# MCU_PSoC_Rev1_1.net
KiCad netlist of a schematic drawn in Altium Designer
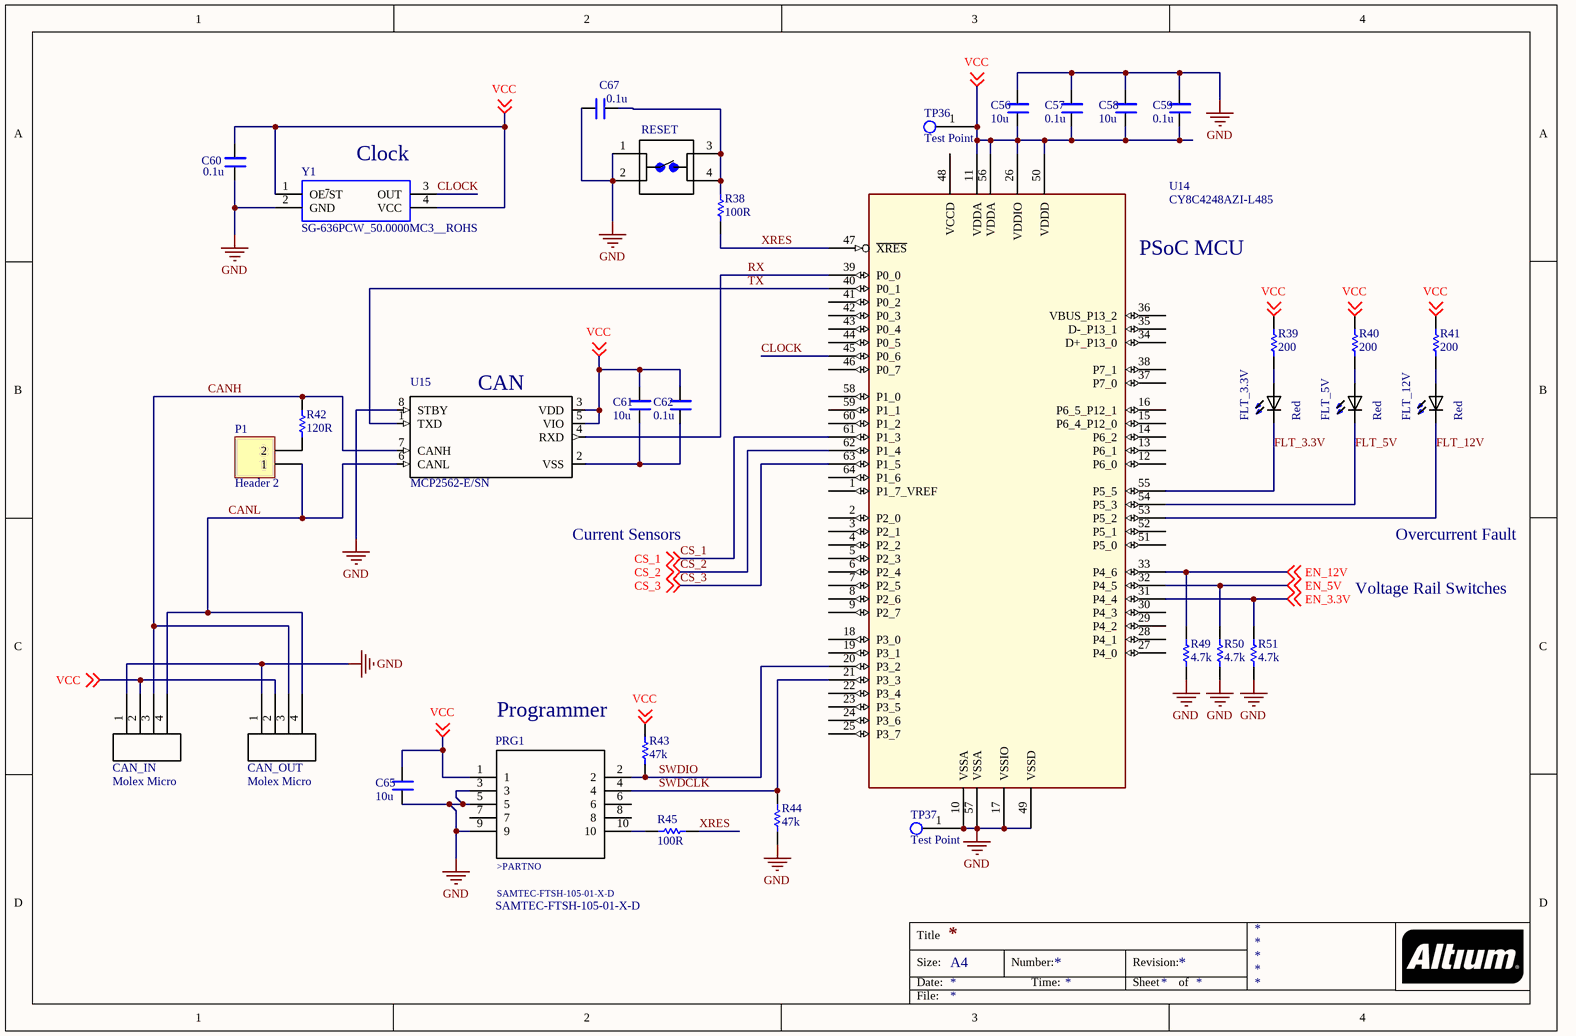
[diagram p0: MCU_PSoC_Rev1.1.SchDoc]

(export (version "E")
  (design (tool "Eeschema 10.0.6"))
  (components
    (comp (ref "C56")
      (value "10u")
      (footprint "*CAPC2012X88N")
      (description "100pF Â±5% 250V Ceramic Capacitor C0G, NP0 0805 _2012 Metric_")
      (fields (field (name "MF") "KEMET") (field (name "DIGI-KEY_PART_NUMBER") "399-15000-1-ND"))
      (libsource (lib "C0805C101JAGAC7800") (part "C0805C101JAGAC7800"))
    )
    (comp (ref "C57")
      (value "0.1u")
      (footprint "*CAPC2012X88N")
      (description "100pF Â±5% 250V Ceramic Capacitor C0G, NP0 0805 _2012 Metric_")
      (fields (field (name "MF") "KEMET") (field (name "DIGI-KEY_PART_NUMBER") "399-15000-1-ND"))
      (libsource (lib "C0805C101JAGAC7800") (part "C0805C101JAGAC7800"))
    )
    (comp (ref "C58")
      (value "10u")
      (footprint "*CAPC2012X88N")
      (description "100pF Â±5% 250V Ceramic Capacitor C0G, NP0 0805 _2012 Metric_")
      (fields (field (name "MF") "KEMET") (field (name "DIGI-KEY_PART_NUMBER") "399-15000-1-ND"))
      (libsource (lib "C0805C101JAGAC7800") (part "C0805C101JAGAC7800"))
    )
    (comp (ref "C59")
      (value "0.1u")
      (footprint "*CAPC2012X88N")
      (description "100pF Â±5% 250V Ceramic Capacitor C0G, NP0 0805 _2012 Metric_")
      (fields (field (name "MF") "KEMET") (field (name "DIGI-KEY_PART_NUMBER") "399-15000-1-ND"))
      (libsource (lib "C0805C101JAGAC7800") (part "C0805C101JAGAC7800"))
    )
    (comp (ref "C60")
      (value "0.1u")
      (footprint "*CAPC2012X88N")
      (description "100pF Â±5% 250V Ceramic Capacitor C0G, NP0 0805 _2012 Metric_")
      (fields (field (name "MF") "KEMET") (field (name "DIGI-KEY_PART_NUMBER") "399-15000-1-ND"))
      (libsource (lib "C0805C101JAGAC7800") (part "C0805C101JAGAC7800"))
    )
    (comp (ref "C61")
      (value "10u")
      (footprint "*CAPC2012X88N")
      (description "100pF Â±5% 250V Ceramic Capacitor C0G, NP0 0805 _2012 Metric_")
      (fields (field (name "MF") "KEMET") (field (name "DIGI-KEY_PART_NUMBER") "399-15000-1-ND"))
      (libsource (lib "C0805C101JAGAC7800") (part "C0805C101JAGAC7800"))
    )
    (comp (ref "C62")
      (value "0.1u")
      (footprint "*CAPC2012X88N")
      (description "100pF Â±5% 250V Ceramic Capacitor C0G, NP0 0805 _2012 Metric_")
      (fields (field (name "MF") "KEMET") (field (name "DIGI-KEY_PART_NUMBER") "399-15000-1-ND"))
      (libsource (lib "C0805C101JAGAC7800") (part "C0805C101JAGAC7800"))
    )
    (comp (ref "C65")
      (value "10u")
      (footprint "*CAPC2012X88N")
      (description "100pF Â±5% 250V Ceramic Capacitor C0G, NP0 0805 _2012 Metric_")
      (fields (field (name "MF") "KEMET") (field (name "DIGI-KEY_PART_NUMBER") "399-15000-1-ND"))
      (libsource (lib "C0805C101JAGAC7800") (part "C0805C101JAGAC7800"))
    )
    (comp (ref "C67")
      (value "0.1u")
      (footprint "*CAPC2012X88N")
      (description "100pF Â±5% 250V Ceramic Capacitor C0G, NP0 0805 _2012 Metric_")
      (fields (field (name "MF") "KEMET") (field (name "DIGI-KEY_PART_NUMBER") "399-15000-1-ND"))
      (libsource (lib "C0805C101JAGAC7800") (part "C0805C101JAGAC7800"))
    )
    (comp (ref "CAN_IN")
      (value "Molex Micro")
      (footprint "0430450427")
      (description "Molex micro-fit 3.0 dual row header. P/N 0430450427")
      (libsource (lib "Connector Schematic Symbols") (part "Molex micro-fit 4-pin (Single row schematic)"))
    )
    (comp (ref "CAN_OUT")
      (value "Molex Micro")
      (footprint "0430450427")
      (description "Molex micro-fit 3.0 dual row header. P/N 0430450427")
      (libsource (lib "Connector Schematic Symbols") (part "Molex micro-fit 4-pin (Single row schematic)"))
    )
    (comp (ref "FLT_3.3V")
      (value "Red")
      (footprint "*DIOC200X125X110_LTST-C171KSKT(Primary)")
      (description "Yellow 2 x 1.25 x 0.8 mm 130Â° Water Clear 50 mcd 2 V LED SMT")
      (fields (field (name "MP") "LTST-C171KSKT") (field (name "DIGI-KEY_PART_NUMBER") "160-1428-1-ND"))
      (libsource (lib "LTST-C171KSKT") (part "LTST-C171KSKT"))
    )
    (comp (ref "FLT_5V")
      (value "Red")
      (footprint "*DIOC200X125X110_LTST-C171KSKT(Primary)")
      (description "Yellow 2 x 1.25 x 0.8 mm 130Â° Water Clear 50 mcd 2 V LED SMT")
      (fields (field (name "MP") "LTST-C171KSKT") (field (name "DIGI-KEY_PART_NUMBER") "160-1428-1-ND"))
      (libsource (lib "LTST-C171KSKT") (part "LTST-C171KSKT"))
    )
    (comp (ref "FLT_12V")
      (value "Red")
      (footprint "*DIOC200X125X110_LTST-C171KSKT(Primary)")
      (description "Yellow 2 x 1.25 x 0.8 mm 130Â° Water Clear 50 mcd 2 V LED SMT")
      (fields (field (name "MP") "LTST-C171KSKT") (field (name "DIGI-KEY_PART_NUMBER") "160-1428-1-ND"))
      (libsource (lib "LTST-C171KSKT") (part "LTST-C171KSKT"))
    )
    (comp (ref "P1")
      (value "Header 2")
      (footprint "HDR1X2")
      (description "Header, 2-Pin")
      (fields (field (name "PUBLISHER") "Altium Limited"))
      (libsource (lib "Power Distribution") (part "Header 2"))
    )
    (comp (ref "PRG1")
      (value "SAMTEC-FTSH-105-01-X-D")
      (footprint "SAMTEC-FTSH-105-01-X-D")
      (description "SAMTEC-FTSH-105-01-X-D. Shrouded 10-pin header with .05 in pitch.")
      (libsource (lib "Power Distribution") (part "SAMTEC-FTSH-105-01-X-D"))
    )
    (comp (ref "R38")
      (value "100R")
      (footprint "RESC0805(2012)_M")
      (description "8M06 0.125W 1% 0805 (2012 Metric)  SMD")
      (fields (field (name "POWER") "0.125 W") (field (name "TOLERANCE") "1 %"))
      (libsource (lib "Altium Content Vault") (part "RES"))
    )
    (comp (ref "R39")
      (value "200")
      (footprint "RESC0805(2012)_M")
      (description "8M06 0.125W 1% 0805 (2012 Metric)  SMD")
      (fields (field (name "POWER") "0.125 W") (field (name "TOLERANCE") "1 %"))
      (libsource (lib "Altium Content Vault") (part "RES"))
    )
    (comp (ref "R40")
      (value "200")
      (footprint "RESC0805(2012)_M")
      (description "8M06 0.125W 1% 0805 (2012 Metric)  SMD")
      (fields (field (name "POWER") "0.125 W") (field (name "TOLERANCE") "1 %"))
      (libsource (lib "Altium Content Vault") (part "RES"))
    )
    (comp (ref "R41")
      (value "200")
      (footprint "RESC0805(2012)_M")
      (description "8M06 0.125W 1% 0805 (2012 Metric)  SMD")
      (fields (field (name "POWER") "0.125 W") (field (name "TOLERANCE") "1 %"))
      (libsource (lib "Altium Content Vault") (part "RES"))
    )
    (comp (ref "R42")
      (value "120R")
      (footprint "RESC0805(2012)_N")
      (description "120R 0.125W 5% 0805 (2012 Metric)  SMD")
      (fields (field (name "TOLERANCE") "5 %") (field (name "POWER") "0.125 W"))
      (libsource (lib "CAN Termination Resistor 0805") (part "120R 5% 0805"))
    )
    (comp (ref "R43")
      (value "47k")
      (footprint "RESC0805(2012)_M")
      (description "8M06 0.125W 1% 0805 (2012 Metric)  SMD")
      (fields (field (name "POWER") "0.125 W") (field (name "TOLERANCE") "1 %"))
      (libsource (lib "Altium Content Vault") (part "RES"))
    )
    (comp (ref "R44")
      (value "47k")
      (footprint "RESC0805(2012)_M")
      (description "8M06 0.125W 1% 0805 (2012 Metric)  SMD")
      (fields (field (name "POWER") "0.125 W") (field (name "TOLERANCE") "1 %"))
      (libsource (lib "Altium Content Vault") (part "RES"))
    )
    (comp (ref "R45")
      (value "100R")
      (footprint "RESC0805(2012)_M")
      (description "8M06 0.125W 1% 0805 (2012 Metric)  SMD")
      (fields (field (name "POWER") "0.125 W") (field (name "TOLERANCE") "1 %"))
      (libsource (lib "Altium Content Vault") (part "RES"))
    )
    (comp (ref "R49")
      (value "4.7k")
      (footprint "RESC0805(2012)_M")
      (description "8M06 0.125W 1% 0805 (2012 Metric)  SMD")
      (fields (field (name "POWER") "0.125 W") (field (name "TOLERANCE") "1 %"))
      (libsource (lib "Altium Content Vault") (part "RES"))
    )
    (comp (ref "R50")
      (value "4.7k")
      (footprint "RESC0805(2012)_M")
      (description "8M06 0.125W 1% 0805 (2012 Metric)  SMD")
      (fields (field (name "POWER") "0.125 W") (field (name "TOLERANCE") "1 %"))
      (libsource (lib "Altium Content Vault") (part "RES"))
    )
    (comp (ref "R51")
      (value "4.7k")
      (footprint "RESC0805(2012)_M")
      (description "8M06 0.125W 1% 0805 (2012 Metric)  SMD")
      (fields (field (name "POWER") "0.125 W") (field (name "TOLERANCE") "1 %"))
      (libsource (lib "Altium Content Vault") (part "RES"))
    )
    (comp (ref "RESET")
      (value "1825910-7")
      (footprint "Switch 6mm 24V (NO)")
      (description "FSM4JAH=6MM TACT SWITCH, HIGH TEMP")
      (fields (field (name "MF") "TE Connectivity") (field (name "DIGI-KEY_PART_NUMBER") "450-1804-ND"))
      (libsource (lib "Switch 6mm 24V") (part "Switch 6mm 24V (NO)"))
    )
    (comp (ref "TP36")
      (value "Test Point")
      (footprint "Test Point Through-hole")
      (libsource (lib "Test Points") (part "Test Point"))
    )
    (comp (ref "TP37")
      (value "Test Point")
      (footprint "Test Point Through-hole")
      (libsource (lib "Test Points") (part "Test Point"))
    )
    (comp (ref "U14")
      (value "CY8C4248AZI-L485")
      (footprint "TQFP50P1200X1200X160-64N")
      (libsource (lib "PSOC") (part "CY8C4248AZI-L485"))
    )
    (comp (ref "U15")
      (value "MCP2562-E/SN")
      (footprint "SOIC127P600X175-8N")
      (description "Microchip MCP2562-E/SN, CAN Transceiver 1MBps 1-channel IEC 61000-4-2, 8-Pin SOIC")
      (fields (field (name "MF") "Microchip"))
      (libsource (lib "CAN Tranceiver") (part "MCP2562-E/SN"))
    )
    (comp (ref "Y1")
      (value "SG-636PCW_50.0000MC3__ROHS")
      (footprint "SG-636")
      (description "Standard Clock Oscillators 50MHz 3.3Volt 100ppm -20C +70C")
      (fields (field (name "MANUFACTURER_PART_NUMBER") "SG-636PCW 50.0000MC3: ROHS"))
      (libsource (lib "Oscillator") (part "SG-636"))
    )
  )
  (nets
    (net (code "1") (name "/CANH") (class "Default")
      (node (ref "CAN_IN") (pin "3") (pintype "passive"))
      (node (ref "CAN_OUT") (pin "3") (pintype "passive"))
      (node (ref "R42") (pin "2") (pinfunction "2_2") (pintype "passive"))
      (node (ref "U15") (pin "7") (pinfunction "CANH_7") (pintype "input"))
    )
    (net (code "2") (name "/CANL") (class "Default")
      (node (ref "CAN_IN") (pin "4") (pintype "passive"))
      (node (ref "CAN_OUT") (pin "4") (pintype "passive"))
      (node (ref "P1") (pin "1") (pinfunction "1_1") (pintype "passive"))
      (node (ref "U15") (pin "6") (pinfunction "CANL_6") (pintype "input"))
    )
    (net (code "3") (name "/CLOCK") (class "Default")
      (node (ref "U14") (pin "45") (pinfunction "P0_6_45") (pintype "bidirectional"))
      (node (ref "Y1") (pin "3") (pinfunction "OUT_3") (pintype "passive"))
    )
    (net (code "4") (name "/FLT_3.3V") (class "Default")
      (node (ref "FLT_3.3V") (pin "NEG") (pinfunction "NEG_NEG") (pintype "passive"))
      (node (ref "U14") (pin "55") (pinfunction "P5_5_55") (pintype "bidirectional"))
    )
    (net (code "5") (name "/FLT_5V") (class "Default")
      (node (ref "FLT_5V") (pin "NEG") (pinfunction "NEG_NEG") (pintype "passive"))
      (node (ref "U14") (pin "54") (pinfunction "P5_3_54") (pintype "bidirectional"))
    )
    (net (code "6") (name "/FLT_12V") (class "Default")
      (node (ref "FLT_12V") (pin "NEG") (pinfunction "NEG_NEG") (pintype "passive"))
      (node (ref "U14") (pin "53") (pinfunction "P5_2_53") (pintype "bidirectional"))
    )
    (net (code "7") (name "/RX") (class "Default")
      (node (ref "U14") (pin "39") (pinfunction "P0_0_39") (pintype "bidirectional"))
      (node (ref "U15") (pin "4") (pinfunction "RXD_4") (pintype "output"))
    )
    (net (code "8") (name "/SWDCLK") (class "Default")
      (node (ref "PRG1") (pin "4") (pinfunction "4_4") (pintype "passive"))
      (node (ref "R44") (pin "1") (pinfunction "1_1") (pintype "passive"))
      (node (ref "U14") (pin "21") (pinfunction "P3_3_21") (pintype "bidirectional"))
    )
    (net (code "9") (name "/SWDIO") (class "Default")
      (node (ref "PRG1") (pin "2") (pinfunction "2_2") (pintype "passive"))
      (node (ref "R43") (pin "2") (pinfunction "2_2") (pintype "passive"))
      (node (ref "U14") (pin "20") (pinfunction "P3_2_20") (pintype "bidirectional"))
    )
    (net (code "10") (name "/TX") (class "Default")
      (node (ref "U14") (pin "40") (pinfunction "P0_1_40") (pintype "bidirectional"))
      (node (ref "U15") (pin "1") (pinfunction "TXD_1") (pintype "input"))
    )
    (net (code "11") (name "/XRES") (class "Default")
      (node (ref "R38") (pin "2") (pinfunction "2_2") (pintype "passive"))
      (node (ref "R45") (pin "1") (pinfunction "1_1") (pintype "passive"))
      (node (ref "U14") (pin "47") (pinfunction "~{XRES}_47") (pintype "input"))
    )
    (net (code "12") (name "CS_1") (class "Default")
      (node (ref "U14") (pin "61") (pinfunction "P1_3_61") (pintype "bidirectional"))
    )
    (net (code "13") (name "CS_2") (class "Default")
      (node (ref "U14") (pin "62") (pinfunction "P1_4_62") (pintype "bidirectional"))
    )
    (net (code "14") (name "CS_3") (class "Default")
      (node (ref "U14") (pin "63") (pinfunction "P1_5_63") (pintype "bidirectional"))
    )
    (net (code "15") (name "EN_3.3V") (class "Default")
      (node (ref "R51") (pin "1") (pinfunction "1_1") (pintype "passive"))
      (node (ref "U14") (pin "31") (pinfunction "P4_4_31") (pintype "bidirectional"))
    )
    (net (code "16") (name "EN_5V") (class "Default")
      (node (ref "R50") (pin "1") (pinfunction "1_1") (pintype "passive"))
      (node (ref "U14") (pin "32") (pinfunction "P4_5_32") (pintype "bidirectional"))
    )
    (net (code "17") (name "EN_12V") (class "Default")
      (node (ref "R49") (pin "1") (pinfunction "1_1") (pintype "passive"))
      (node (ref "U14") (pin "33") (pinfunction "P4_6_33") (pintype "bidirectional"))
    )
    (net (code "18") (name "GND") (class "Default")
      (node (ref "C56") (pin "2") (pinfunction "2_2") (pintype "passive"))
      (node (ref "C57") (pin "2") (pinfunction "2_2") (pintype "passive"))
      (node (ref "C58") (pin "2") (pinfunction "2_2") (pintype "passive"))
      (node (ref "C59") (pin "2") (pinfunction "2_2") (pintype "passive"))
      (node (ref "C60") (pin "1") (pinfunction "1_1") (pintype "passive"))
      (node (ref "C65") (pin "1") (pinfunction "1_1") (pintype "passive"))
      (node (ref "C67") (pin "1") (pinfunction "1_1") (pintype "passive"))
      (node (ref "CAN_IN") (pin "1") (pintype "passive"))
      (node (ref "CAN_OUT") (pin "1") (pintype "passive"))
      (node (ref "PRG1") (pin "3") (pinfunction "3_3") (pintype "passive"))
      (node (ref "PRG1") (pin "5") (pinfunction "5_5") (pintype "passive"))
      (node (ref "PRG1") (pin "9") (pinfunction "9_9") (pintype "passive"))
      (node (ref "R44") (pin "2") (pinfunction "2_2") (pintype "passive"))
      (node (ref "R49") (pin "2") (pinfunction "2_2") (pintype "passive"))
      (node (ref "R50") (pin "2") (pinfunction "2_2") (pintype "passive"))
      (node (ref "R51") (pin "2") (pinfunction "2_2") (pintype "passive"))
      (node (ref "RESET") (pin "1") (pinfunction "1_1") (pintype "passive"))
      (node (ref "RESET") (pin "2") (pinfunction "2_2") (pintype "passive"))
      (node (ref "TP37") (pin "1") (pinfunction "1_1") (pintype "passive"))
      (node (ref "U14") (pin "10") (pinfunction "VSSA_10") (pintype "power_in"))
      (node (ref "U14") (pin "17") (pinfunction "VSSIO_17") (pintype "power_in"))
      (node (ref "U14") (pin "49") (pinfunction "VSSD_49") (pintype "power_in"))
      (node (ref "U14") (pin "57") (pinfunction "VSSA_57") (pintype "power_in"))
      (node (ref "U15") (pin "8") (pinfunction "STBY_8") (pintype "input"))
      (node (ref "Y1") (pin "2") (pinfunction "GND_2") (pintype "passive"))
    )
    (net (code "19") (name "Net-(C67-Pad2)") (class "Default")
      (node (ref "C67") (pin "2") (pinfunction "2_2") (pintype "passive"))
      (node (ref "R38") (pin "1") (pinfunction "1_1") (pintype "passive"))
      (node (ref "RESET") (pin "3") (pinfunction "3_3") (pintype "passive"))
      (node (ref "RESET") (pin "4") (pinfunction "4_4") (pintype "passive"))
    )
    (net (code "20") (name "Net-(FLT_3.3V-PadPOS)") (class "Default")
      (node (ref "FLT_3.3V") (pin "POS") (pinfunction "POS_POS") (pintype "passive"))
      (node (ref "R39") (pin "1") (pinfunction "1_1") (pintype "passive"))
    )
    (net (code "21") (name "Net-(FLT_5V-PadPOS)") (class "Default")
      (node (ref "FLT_5V") (pin "POS") (pinfunction "POS_POS") (pintype "passive"))
      (node (ref "R40") (pin "1") (pinfunction "1_1") (pintype "passive"))
    )
    (net (code "22") (name "Net-(FLT_12V-PadPOS)") (class "Default")
      (node (ref "FLT_12V") (pin "POS") (pinfunction "POS_POS") (pintype "passive"))
      (node (ref "R41") (pin "1") (pinfunction "1_1") (pintype "passive"))
    )
    (net (code "23") (name "Net-(P1-Pad2)") (class "Default")
      (node (ref "P1") (pin "2") (pinfunction "2_2") (pintype "passive"))
      (node (ref "R42") (pin "1") (pinfunction "1_1") (pintype "passive"))
    )
    (net (code "24") (name "Net-(PRG1-Pad10)") (class "Default")
      (node (ref "PRG1") (pin "10") (pinfunction "10_10") (pintype "passive"))
      (node (ref "R45") (pin "2") (pinfunction "2_2") (pintype "passive"))
    )
    (net (code "25") (name "Net-(U15-VSS)") (class "Default")
      (node (ref "C61") (pin "1") (pinfunction "1_1") (pintype "passive"))
      (node (ref "C62") (pin "1") (pinfunction "1_1") (pintype "passive"))
      (node (ref "U15") (pin "2") (pinfunction "VSS_2") (pintype "power_in"))
    )
    (net (code "26") (name "VCC") (class "Default")
      (node (ref "C56") (pin "1") (pinfunction "1_1") (pintype "passive"))
      (node (ref "C57") (pin "1") (pinfunction "1_1") (pintype "passive"))
      (node (ref "C58") (pin "1") (pinfunction "1_1") (pintype "passive"))
      (node (ref "C59") (pin "1") (pinfunction "1_1") (pintype "passive"))
      (node (ref "C60") (pin "2") (pinfunction "2_2") (pintype "passive"))
      (node (ref "C61") (pin "2") (pinfunction "2_2") (pintype "passive"))
      (node (ref "C62") (pin "2") (pinfunction "2_2") (pintype "passive"))
      (node (ref "C65") (pin "2") (pinfunction "2_2") (pintype "passive"))
      (node (ref "CAN_IN") (pin "2") (pintype "passive"))
      (node (ref "CAN_OUT") (pin "2") (pintype "passive"))
      (node (ref "PRG1") (pin "1") (pinfunction "1_1") (pintype "passive"))
      (node (ref "R39") (pin "2") (pinfunction "2_2") (pintype "passive"))
      (node (ref "R40") (pin "2") (pinfunction "2_2") (pintype "passive"))
      (node (ref "R41") (pin "2") (pinfunction "2_2") (pintype "passive"))
      (node (ref "R43") (pin "1") (pinfunction "1_1") (pintype "passive"))
      (node (ref "TP36") (pin "1") (pinfunction "1_1") (pintype "passive"))
      (node (ref "U14") (pin "11") (pinfunction "VDDA_11") (pintype "power_in"))
      (node (ref "U14") (pin "26") (pinfunction "VDDIO_26") (pintype "power_in"))
      (node (ref "U14") (pin "50") (pinfunction "VDDD_50") (pintype "power_in"))
      (node (ref "U14") (pin "56") (pinfunction "VDDA_56") (pintype "power_in"))
      (node (ref "U15") (pin "3") (pinfunction "VDD_3") (pintype "power_in"))
      (node (ref "U15") (pin "5") (pinfunction "VIO_5") (pintype "power_in"))
      (node (ref "Y1") (pin "1") (pinfunction "OE~{/}ST_1") (pintype "passive"))
      (node (ref "Y1") (pin "4") (pinfunction "VCC_4") (pintype "power_in"))
    )
    (net (code "27") (name "unconnected-(PRG1-Pad6)") (class "Default")
      (node (ref "PRG1") (pin "6") (pinfunction "6_6") (pintype "passive"))
    )
    (net (code "28") (name "unconnected-(PRG1-Pad7)") (class "Default")
      (node (ref "PRG1") (pin "7") (pinfunction "7_7") (pintype "passive"))
    )
    (net (code "29") (name "unconnected-(PRG1-Pad8)") (class "Default")
      (node (ref "PRG1") (pin "8") (pinfunction "8_8") (pintype "passive"))
    )
    (net (code "30") (name "unconnected-(U14-D+_P13_0-Pad34)") (class "Default")
      (node (ref "U14") (pin "34") (pinfunction "D+_P13_0_34") (pintype "bidirectional"))
    )
    (net (code "31") (name "unconnected-(U14-D-_P13_1-Pad35)") (class "Default")
      (node (ref "U14") (pin "35") (pinfunction "D-_P13_1_35") (pintype "bidirectional"))
    )
    (net (code "32") (name "unconnected-(U14-P0_2-Pad41)") (class "Default")
      (node (ref "U14") (pin "41") (pinfunction "P0_2_41") (pintype "bidirectional"))
    )
    (net (code "33") (name "unconnected-(U14-P0_3-Pad42)") (class "Default")
      (node (ref "U14") (pin "42") (pinfunction "P0_3_42") (pintype "bidirectional"))
    )
    (net (code "34") (name "unconnected-(U14-P0_4-Pad43)") (class "Default")
      (node (ref "U14") (pin "43") (pinfunction "P0_4_43") (pintype "bidirectional"))
    )
    (net (code "35") (name "unconnected-(U14-P0_5-Pad44)") (class "Default")
      (node (ref "U14") (pin "44") (pinfunction "P0_5_44") (pintype "bidirectional"))
    )
    (net (code "36") (name "unconnected-(U14-P0_7-Pad46)") (class "Default")
      (node (ref "U14") (pin "46") (pinfunction "P0_7_46") (pintype "bidirectional"))
    )
    (net (code "37") (name "unconnected-(U14-P1_0-Pad58)") (class "Default")
      (node (ref "U14") (pin "58") (pinfunction "P1_0_58") (pintype "bidirectional"))
    )
    (net (code "38") (name "unconnected-(U14-P1_1-Pad59)") (class "Default")
      (node (ref "U14") (pin "59") (pinfunction "P1_1_59") (pintype "bidirectional"))
    )
    (net (code "39") (name "unconnected-(U14-P1_2-Pad60)") (class "Default")
      (node (ref "U14") (pin "60") (pinfunction "P1_2_60") (pintype "bidirectional"))
    )
    (net (code "40") (name "unconnected-(U14-P1_6-Pad64)") (class "Default")
      (node (ref "U14") (pin "64") (pinfunction "P1_6_64") (pintype "bidirectional"))
    )
    (net (code "41") (name "unconnected-(U14-P1_7_VREF-Pad1)") (class "Default")
      (node (ref "U14") (pin "1") (pinfunction "P1_7_VREF_1") (pintype "bidirectional"))
    )
    (net (code "42") (name "unconnected-(U14-P2_0-Pad2)") (class "Default")
      (node (ref "U14") (pin "2") (pinfunction "P2_0_2") (pintype "bidirectional"))
    )
    (net (code "43") (name "unconnected-(U14-P2_1-Pad3)") (class "Default")
      (node (ref "U14") (pin "3") (pinfunction "P2_1_3") (pintype "bidirectional"))
    )
    (net (code "44") (name "unconnected-(U14-P2_2-Pad4)") (class "Default")
      (node (ref "U14") (pin "4") (pinfunction "P2_2_4") (pintype "bidirectional"))
    )
    (net (code "45") (name "unconnected-(U14-P2_3-Pad5)") (class "Default")
      (node (ref "U14") (pin "5") (pinfunction "P2_3_5") (pintype "bidirectional"))
    )
    (net (code "46") (name "unconnected-(U14-P2_4-Pad6)") (class "Default")
      (node (ref "U14") (pin "6") (pinfunction "P2_4_6") (pintype "bidirectional"))
    )
    (net (code "47") (name "unconnected-(U14-P2_5-Pad7)") (class "Default")
      (node (ref "U14") (pin "7") (pinfunction "P2_5_7") (pintype "bidirectional"))
    )
    (net (code "48") (name "unconnected-(U14-P2_6-Pad8)") (class "Default")
      (node (ref "U14") (pin "8") (pinfunction "P2_6_8") (pintype "bidirectional"))
    )
    (net (code "49") (name "unconnected-(U14-P2_7-Pad9)") (class "Default")
      (node (ref "U14") (pin "9") (pinfunction "P2_7_9") (pintype "bidirectional"))
    )
    (net (code "50") (name "unconnected-(U14-P3_0-Pad18)") (class "Default")
      (node (ref "U14") (pin "18") (pinfunction "P3_0_18") (pintype "bidirectional"))
    )
    (net (code "51") (name "unconnected-(U14-P3_1-Pad19)") (class "Default")
      (node (ref "U14") (pin "19") (pinfunction "P3_1_19") (pintype "bidirectional"))
    )
    (net (code "52") (name "unconnected-(U14-P3_4-Pad22)") (class "Default")
      (node (ref "U14") (pin "22") (pinfunction "P3_4_22") (pintype "bidirectional"))
    )
    (net (code "53") (name "unconnected-(U14-P3_5-Pad23)") (class "Default")
      (node (ref "U14") (pin "23") (pinfunction "P3_5_23") (pintype "bidirectional"))
    )
    (net (code "54") (name "unconnected-(U14-P3_6-Pad24)") (class "Default")
      (node (ref "U14") (pin "24") (pinfunction "P3_6_24") (pintype "bidirectional"))
    )
    (net (code "55") (name "unconnected-(U14-P3_7-Pad25)") (class "Default")
      (node (ref "U14") (pin "25") (pinfunction "P3_7_25") (pintype "bidirectional"))
    )
    (net (code "56") (name "unconnected-(U14-P4_0-Pad27)") (class "Default")
      (node (ref "U14") (pin "27") (pinfunction "P4_0_27") (pintype "bidirectional"))
    )
    (net (code "57") (name "unconnected-(U14-P4_1-Pad28)") (class "Default")
      (node (ref "U14") (pin "28") (pinfunction "P4_1_28") (pintype "bidirectional"))
    )
    (net (code "58") (name "unconnected-(U14-P4_2-Pad29)") (class "Default")
      (node (ref "U14") (pin "29") (pinfunction "P4_2_29") (pintype "bidirectional"))
    )
    (net (code "59") (name "unconnected-(U14-P4_3-Pad30)") (class "Default")
      (node (ref "U14") (pin "30") (pinfunction "P4_3_30") (pintype "bidirectional"))
    )
    (net (code "60") (name "unconnected-(U14-P5_0-Pad51)") (class "Default")
      (node (ref "U14") (pin "51") (pinfunction "P5_0_51") (pintype "bidirectional"))
    )
    (net (code "61") (name "unconnected-(U14-P5_1-Pad52)") (class "Default")
      (node (ref "U14") (pin "52") (pinfunction "P5_1_52") (pintype "bidirectional"))
    )
    (net (code "62") (name "unconnected-(U14-P6_0-Pad12)") (class "Default")
      (node (ref "U14") (pin "12") (pinfunction "P6_0_12") (pintype "bidirectional"))
    )
    (net (code "63") (name "unconnected-(U14-P6_1-Pad13)") (class "Default")
      (node (ref "U14") (pin "13") (pinfunction "P6_1_13") (pintype "bidirectional"))
    )
    (net (code "64") (name "unconnected-(U14-P6_2-Pad14)") (class "Default")
      (node (ref "U14") (pin "14") (pinfunction "P6_2_14") (pintype "bidirectional"))
    )
    (net (code "65") (name "unconnected-(U14-P6_4_P12_0-Pad15)") (class "Default")
      (node (ref "U14") (pin "15") (pinfunction "P6_4_P12_0_15") (pintype "bidirectional"))
    )
    (net (code "66") (name "unconnected-(U14-P6_5_P12_1-Pad16)") (class "Default")
      (node (ref "U14") (pin "16") (pinfunction "P6_5_P12_1_16") (pintype "bidirectional"))
    )
    (net (code "67") (name "unconnected-(U14-P7_0-Pad37)") (class "Default")
      (node (ref "U14") (pin "37") (pinfunction "P7_0_37") (pintype "bidirectional"))
    )
    (net (code "68") (name "unconnected-(U14-P7_1-Pad38)") (class "Default")
      (node (ref "U14") (pin "38") (pinfunction "P7_1_38") (pintype "bidirectional"))
    )
    (net (code "69") (name "unconnected-(U14-VBUS_P13_2-Pad36)") (class "Default")
      (node (ref "U14") (pin "36") (pinfunction "VBUS_P13_2_36") (pintype "bidirectional"))
    )
    (net (code "70") (name "unconnected-(U14-VCCD-Pad48)") (class "Default")
      (node (ref "U14") (pin "48") (pinfunction "VCCD_48") (pintype "power_in"))
    )
  )
)
